# MonochromeVGA.net
KiCad netlist of a schematic drawn in EAGLE
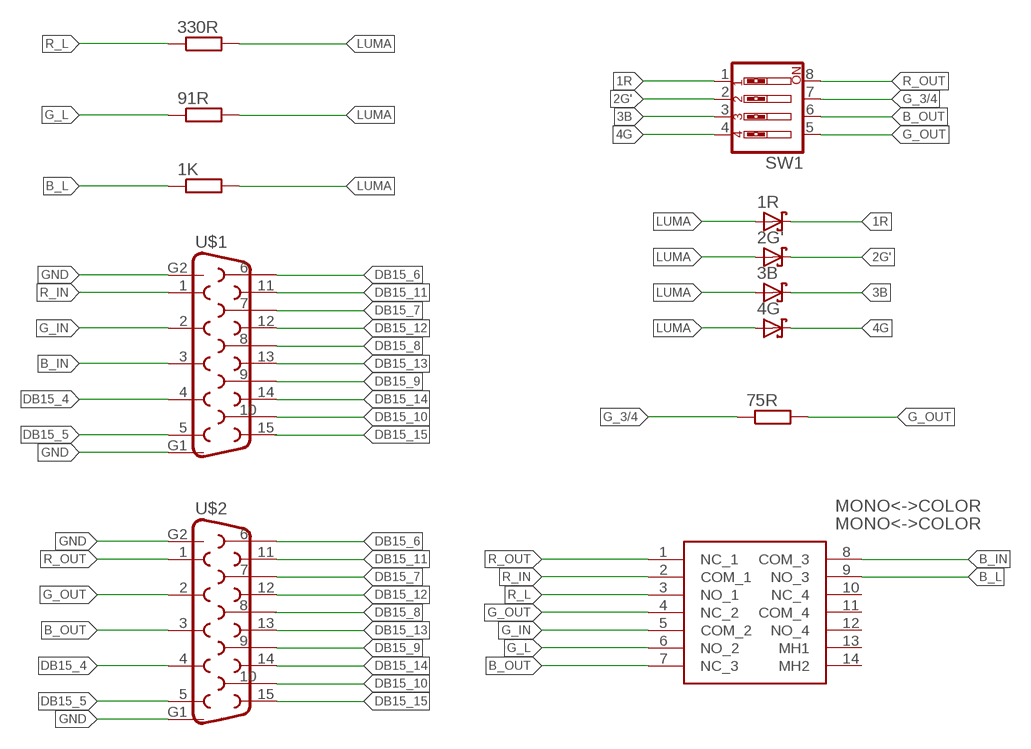
[diagram p0: schematic, sheet 1]

(export (version "E")
  (design (tool "Eeschema 10.0.6"))
  (components
    (comp (ref "1K")
      (value "R-EU_0204/5")
      (footprint "eagle-import:0204_5")
      (libsource (lib "eagle-import") (part "R-EU_0204/5"))
    )
    (comp (ref "1R")
      (value "SCHOTTKY-DIODEDO35-7")
      (footprint "eagle-import:DO35-7")
      (libsource (lib "eagle-import") (part "SCHOTTKY-DIODEDO35-7"))
    )
    (comp (ref "2G'")
      (value "SCHOTTKY-DIODEDO35-7")
      (footprint "eagle-import:DO35-7")
      (libsource (lib "eagle-import") (part "SCHOTTKY-DIODEDO35-7"))
    )
    (comp (ref "3B")
      (value "SCHOTTKY-DIODEDO35-7")
      (footprint "eagle-import:DO35-7")
      (libsource (lib "eagle-import") (part "SCHOTTKY-DIODEDO35-7"))
    )
    (comp (ref "4G")
      (value "SCHOTTKY-DIODEDO35-7")
      (footprint "eagle-import:DO35-7")
      (libsource (lib "eagle-import") (part "SCHOTTKY-DIODEDO35-7"))
    )
    (comp (ref "75R")
      (value "R-EU_0204/5")
      (footprint "eagle-import:0204_5")
      (libsource (lib "eagle-import") (part "R-EU_0204/5"))
    )
    (comp (ref "91R")
      (value "R-EU_0204/5")
      (footprint "eagle-import:0204_5")
      (libsource (lib "eagle-import") (part "R-EU_0204/5"))
    )
    (comp (ref "330R")
      (value "R-EU_0204/5")
      (footprint "eagle-import:0204_5")
      (libsource (lib "eagle-import") (part "R-EU_0204/5"))
    )
    (comp (ref "MONO<->COLOR")
      (value "MONO<->COLOR")
      (footprint "eagle-import:EG4208A")
      (fields
        (field (name "MANUFACTURER_PART_NUMBER") "EG4208A")
        (field (name "MOUSER_PART_NUMBER") "612-EG4208A")
      )
      (libsource (lib "eagle-import") (part "EG4208A"))
    )
    (comp (ref "SW1")
      (value "SW_DIP-4")
      (footprint "eagle-import:EDG-04")
      (libsource (lib "eagle-import") (part "SW_DIP-4"))
    )
    (comp (ref "U$1")
      (value "DB15")
      (footprint "eagle-import:DB15")
      (libsource (lib "eagle-import") (part "DB15"))
    )
    (comp (ref "U$2")
      (value "DB15")
      (footprint "eagle-import:DB15")
      (libsource (lib "eagle-import") (part "DB15"))
    )
  )
  (nets
    (net (code "1") (name "1R") (class "Default")
      (node (ref "1R") (pin "C") (pinfunction "C_C") (pintype "passive"))
      (node (ref "SW1") (pin "1") (pinfunction "1_1") (pintype "passive"))
    )
    (net (code "2") (name "2G'") (class "Default")
      (node (ref "2G'") (pin "C") (pinfunction "C_C") (pintype "passive"))
      (node (ref "SW1") (pin "2") (pinfunction "2_2") (pintype "passive"))
    )
    (net (code "3") (name "3B") (class "Default")
      (node (ref "3B") (pin "C") (pinfunction "C_C") (pintype "passive"))
      (node (ref "SW1") (pin "3") (pinfunction "3_3") (pintype "passive"))
    )
    (net (code "4") (name "4G") (class "Default")
      (node (ref "4G") (pin "C") (pinfunction "C_C") (pintype "passive"))
      (node (ref "SW1") (pin "4") (pinfunction "4_4") (pintype "passive"))
    )
    (net (code "5") (name "B_IN") (class "Default")
      (node (ref "MONO<->COLOR") (pin "8") (pinfunction "COM_3_8") (pintype "bidirectional"))
      (node (ref "U$1") (pin "3") (pinfunction "3_3") (pintype "passive"))
    )
    (net (code "6") (name "B_L") (class "Default")
      (node (ref "1K") (pin "1") (pinfunction "1_1") (pintype "passive"))
      (node (ref "MONO<->COLOR") (pin "9") (pinfunction "NO_3_9") (pintype "bidirectional"))
    )
    (net (code "7") (name "B_OUT") (class "Default")
      (node (ref "MONO<->COLOR") (pin "7") (pinfunction "NC_3_7") (pintype "bidirectional"))
      (node (ref "SW1") (pin "6") (pinfunction "6_6") (pintype "passive"))
      (node (ref "U$2") (pin "3") (pinfunction "3_3") (pintype "passive"))
    )
    (net (code "8") (name "DB15_4") (class "Default")
      (node (ref "U$1") (pin "4") (pinfunction "4_4") (pintype "passive"))
      (node (ref "U$2") (pin "4") (pinfunction "4_4") (pintype "passive"))
    )
    (net (code "9") (name "DB15_5") (class "Default")
      (node (ref "U$1") (pin "5") (pinfunction "5_5") (pintype "passive"))
      (node (ref "U$2") (pin "5") (pinfunction "5_5") (pintype "passive"))
    )
    (net (code "10") (name "DB15_6") (class "Default")
      (node (ref "U$1") (pin "6") (pinfunction "6_6") (pintype "passive"))
      (node (ref "U$2") (pin "6") (pinfunction "6_6") (pintype "passive"))
    )
    (net (code "11") (name "DB15_7") (class "Default")
      (node (ref "U$1") (pin "7") (pinfunction "7_7") (pintype "passive"))
      (node (ref "U$2") (pin "7") (pinfunction "7_7") (pintype "passive"))
    )
    (net (code "12") (name "DB15_8") (class "Default")
      (node (ref "U$1") (pin "8") (pinfunction "8_8") (pintype "passive"))
      (node (ref "U$2") (pin "8") (pinfunction "8_8") (pintype "passive"))
    )
    (net (code "13") (name "DB15_9") (class "Default")
      (node (ref "U$1") (pin "9") (pinfunction "9_9") (pintype "passive"))
      (node (ref "U$2") (pin "9") (pinfunction "9_9") (pintype "passive"))
    )
    (net (code "14") (name "DB15_10") (class "Default")
      (node (ref "U$1") (pin "10") (pinfunction "10_10") (pintype "passive"))
      (node (ref "U$2") (pin "10") (pinfunction "10_10") (pintype "passive"))
    )
    (net (code "15") (name "DB15_11") (class "Default")
      (node (ref "U$1") (pin "11") (pinfunction "11_11") (pintype "passive"))
      (node (ref "U$2") (pin "11") (pinfunction "11_11") (pintype "passive"))
    )
    (net (code "16") (name "DB15_12") (class "Default")
      (node (ref "U$1") (pin "12") (pinfunction "12_12") (pintype "passive"))
      (node (ref "U$2") (pin "12") (pinfunction "12_12") (pintype "passive"))
    )
    (net (code "17") (name "DB15_13") (class "Default")
      (node (ref "U$1") (pin "13") (pinfunction "13_13") (pintype "passive"))
      (node (ref "U$2") (pin "13") (pinfunction "13_13") (pintype "passive"))
    )
    (net (code "18") (name "DB15_14") (class "Default")
      (node (ref "U$1") (pin "14") (pinfunction "14_14") (pintype "passive"))
      (node (ref "U$2") (pin "14") (pinfunction "14_14") (pintype "passive"))
    )
    (net (code "19") (name "DB15_15") (class "Default")
      (node (ref "U$1") (pin "15") (pinfunction "15_15") (pintype "passive"))
      (node (ref "U$2") (pin "15") (pinfunction "15_15") (pintype "passive"))
    )
    (net (code "20") (name "GND") (class "Default")
      (node (ref "U$1") (pin "G1") (pinfunction "G2_G1") (pintype "passive"))
      (node (ref "U$1") (pin "G2") (pinfunction "G1_G2") (pintype "passive"))
      (node (ref "U$2") (pin "G1") (pinfunction "G2_G1") (pintype "passive"))
      (node (ref "U$2") (pin "G2") (pinfunction "G1_G2") (pintype "passive"))
    )
    (net (code "21") (name "G_3{slash}4") (class "Default")
      (node (ref "75R") (pin "1") (pinfunction "1_1") (pintype "passive"))
      (node (ref "SW1") (pin "7") (pinfunction "7_7") (pintype "passive"))
    )
    (net (code "22") (name "G_IN") (class "Default")
      (node (ref "MONO<->COLOR") (pin "5") (pinfunction "COM_2_5") (pintype "bidirectional"))
      (node (ref "U$1") (pin "2") (pinfunction "2_2") (pintype "passive"))
    )
    (net (code "23") (name "G_L") (class "Default")
      (node (ref "91R") (pin "1") (pinfunction "1_1") (pintype "passive"))
      (node (ref "MONO<->COLOR") (pin "6") (pinfunction "NO_2_6") (pintype "bidirectional"))
    )
    (net (code "24") (name "G_OUT") (class "Default")
      (node (ref "75R") (pin "2") (pinfunction "2_2") (pintype "passive"))
      (node (ref "MONO<->COLOR") (pin "4") (pinfunction "NC_2_4") (pintype "bidirectional"))
      (node (ref "SW1") (pin "5") (pinfunction "5_5") (pintype "passive"))
      (node (ref "U$2") (pin "2") (pinfunction "2_2") (pintype "passive"))
    )
    (net (code "25") (name "LUMA") (class "Default")
      (node (ref "1K") (pin "2") (pinfunction "2_2") (pintype "passive"))
      (node (ref "1R") (pin "A") (pinfunction "A_A") (pintype "passive"))
      (node (ref "2G'") (pin "A") (pinfunction "A_A") (pintype "passive"))
      (node (ref "330R") (pin "2") (pinfunction "2_2") (pintype "passive"))
      (node (ref "3B") (pin "A") (pinfunction "A_A") (pintype "passive"))
      (node (ref "4G") (pin "A") (pinfunction "A_A") (pintype "passive"))
      (node (ref "91R") (pin "2") (pinfunction "2_2") (pintype "passive"))
    )
    (net (code "26") (name "R_IN") (class "Default")
      (node (ref "MONO<->COLOR") (pin "2") (pinfunction "COM_1_2") (pintype "bidirectional"))
      (node (ref "U$1") (pin "1") (pinfunction "1_1") (pintype "passive"))
    )
    (net (code "27") (name "R_L") (class "Default")
      (node (ref "330R") (pin "1") (pinfunction "1_1") (pintype "passive"))
      (node (ref "MONO<->COLOR") (pin "3") (pinfunction "NO_1_3") (pintype "bidirectional"))
    )
    (net (code "28") (name "R_OUT") (class "Default")
      (node (ref "MONO<->COLOR") (pin "1") (pinfunction "NC_1_1") (pintype "bidirectional"))
      (node (ref "SW1") (pin "8") (pinfunction "8_8") (pintype "passive"))
      (node (ref "U$2") (pin "1") (pinfunction "1_1") (pintype "passive"))
    )
    (net (code "29") (name "unconnected-(MONO<->COLOR-COM_4-Pad11)") (class "Default")
      (node (ref "MONO<->COLOR") (pin "11") (pinfunction "COM_4_11") (pintype "bidirectional"))
    )
    (net (code "30") (name "unconnected-(MONO<->COLOR-MH1-Pad13)") (class "Default")
      (node (ref "MONO<->COLOR") (pin "13") (pinfunction "MH1_13") (pintype "bidirectional"))
    )
    (net (code "31") (name "unconnected-(MONO<->COLOR-MH2-Pad14)") (class "Default")
      (node (ref "MONO<->COLOR") (pin "14") (pinfunction "MH2_14") (pintype "bidirectional"))
    )
    (net (code "32") (name "unconnected-(MONO<->COLOR-NC_4-Pad10)") (class "Default")
      (node (ref "MONO<->COLOR") (pin "10") (pinfunction "NC_4_10") (pintype "bidirectional"))
    )
    (net (code "33") (name "unconnected-(MONO<->COLOR-NO_4-Pad12)") (class "Default")
      (node (ref "MONO<->COLOR") (pin "12") (pinfunction "NO_4_12") (pintype "bidirectional"))
    )
  )
)
